# anssipv2.net
KiCad netlist of a schematic drawn in Altium Designer
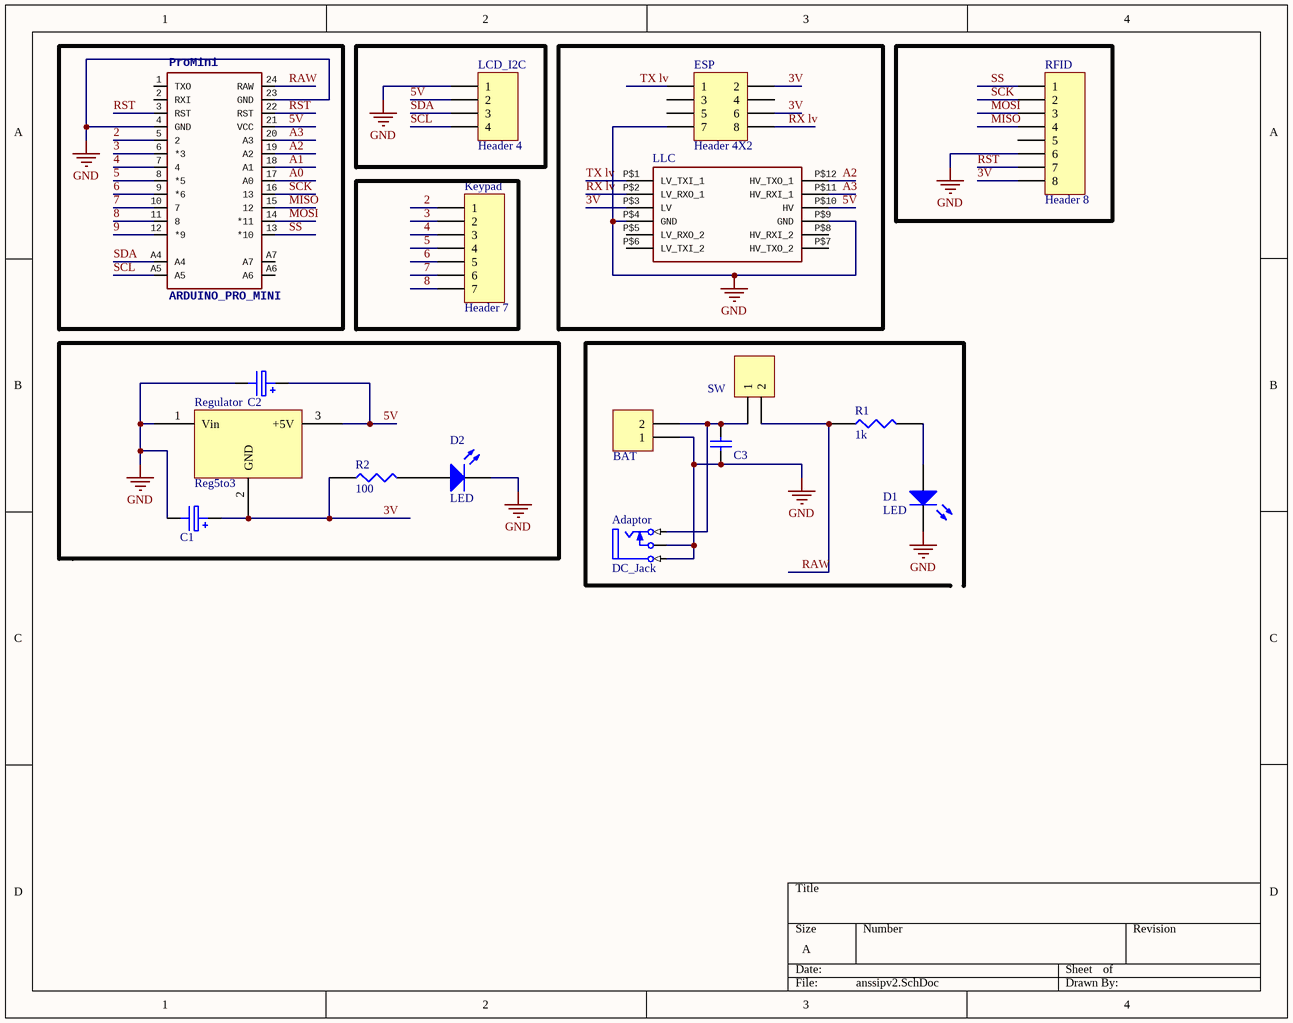
[diagram p0: anssipv2.SchDoc]

(export (version "E")
  (design (tool "Eeschema 10.0.6"))
  (components
    (comp (ref "Adaptor")
      (value "DC_Jack")
      (footprint "My_DC_Jack")
      (fields (field (name "PUBLISHER") "Altium Limited"))
      (libsource (lib "Mylib") (part "DC_Jack"))
    )
    (comp (ref "BAT")
      (value "Power Connector")
      (footprint "My_ Power_Connector")
      (description "white Power Connector")
      (libsource (lib "Mylib") (part "Power Connector"))
    )
    (comp (ref "C1")
      (value "10uF")
      (footprint "CAP 2.5/6.5")
      (description "Electrolytic Capacitor")
      (libsource (lib "Components") (part "CAP2"))
    )
    (comp (ref "C2")
      (value "10uF")
      (footprint "CAP 2.5/6.5")
      (description "Electrolytic Capacitor")
      (libsource (lib "Components") (part "CAP2"))
    )
    (comp (ref "C3")
      (value "Cap")
      (footprint "My_cap100n")
      (description "CAP-100Nf")
      (libsource (lib "Mylib") (part "Cap ceramic"))
    )
    (comp (ref "D1")
      (value "LED")
      (footprint "My_LED3MM")
      (description "Typical INFRARED GaAs LED")
      (fields (field (name "PUBLISHER") "Altium Limited"))
      (libsource (lib "Mylib") (part "LED"))
    )
    (comp (ref "D2")
      (value "LED")
      (footprint "My_LED3MM")
      (description "Typical INFRARED GaAs LED")
      (fields (field (name "PUBLISHER") "Altium Limited"))
      (libsource (lib "Mylib") (part "LED"))
    )
    (comp (ref "ESP")
      (value "Header 4X2")
      (footprint "HDR2X4")
      (description "Header, 4-Pin, Dual row")
      (fields (field (name "PUBLISHER") "Altium Limited"))
      (libsource (lib "Miscellaneous Connectors") (part "Header 4X2"))
    )
    (comp (ref "Keypad")
      (value "Header 7")
      (footprint "HDR1X7")
      (description "Header, 7-Pin")
      (fields (field (name "PUBLISHER") "Altium Limited"))
      (libsource (lib "Miscellaneous Connectors") (part "Header 7"))
    )
    (comp (ref "LCD_I2C")
      (value "Header 4")
      (footprint "HDR1X4")
      (description "Header, 4-Pin")
      (fields (field (name "PUBLISHER") "Altium Limited"))
      (libsource (lib "Miscellaneous Connectors") (part "Header 4"))
    )
    (comp (ref "LLC")
      (value "~")
      (footprint "LOGIC_LEVEL_CONVERTER")
      (libsource (lib "SparkFun-Boards") (part "LOGIC_LEVEL_CONVERTER"))
    )
    (comp (ref "ProMini")
      (value "ARDUINO_PRO_MINI")
      (footprint "ARDUINO_PRO_MINI")
      (libsource (lib "SparkFun-Boards") (part "ARDUINO_PRO_MINI"))
    )
    (comp (ref "R1")
      (value "1k")
      (footprint "My_axial-0.4")
      (description "resistor 1/4 wat")
      (libsource (lib "Mylib") (part "Res"))
    )
    (comp (ref "R2")
      (value "100")
      (footprint "My_axial-0.4")
      (description "resistor 1/4 wat")
      (fields (field (name "Comment") "1k"))
      (libsource (lib "Mylib") (part "Res"))
    )
    (comp (ref "Regulator")
      (value "Reg5to3")
      (footprint "My_TO-220")
      (description "Regulator")
      (libsource (lib "Mylib") (part "7805"))
    )
    (comp (ref "RFID")
      (value "Header 8")
      (footprint "HDR1X8")
      (description "Header, 8-Pin")
      (fields (field (name "PUBLISHER") "Altium Limited"))
      (libsource (lib "Miscellaneous Connectors") (part "Header 8"))
    )
    (comp (ref "SW")
      (value "Power Connector")
      (footprint "My_ Power_Connector")
      (description "white Power Connector")
      (libsource (lib "") (part "Power Connector_1"))
    )
  )
  (nets
    (net (code "1") (name "/2") (class "Default")
      (node (ref "Keypad") (pin "1") (pinfunction "1_1") (pintype "passive"))
      (node (ref "ProMini") (pin "5") (pinfunction "2_5") (pintype "passive"))
    )
    (net (code "2") (name "/3") (class "Default")
      (node (ref "Keypad") (pin "2") (pinfunction "2_2") (pintype "passive"))
      (node (ref "ProMini") (pin "6") (pinfunction "*3_6") (pintype "passive"))
    )
    (net (code "3") (name "/3V") (class "Default")
      (node (ref "C1") (pin "1") (pinfunction "1_1") (pintype "passive"))
      (node (ref "ESP") (pin "2") (pinfunction "2_2") (pintype "passive"))
      (node (ref "ESP") (pin "6") (pinfunction "6_6") (pintype "passive"))
      (node (ref "LLC") (pin "P$3") (pinfunction "LV_P$3") (pintype "passive"))
      (node (ref "R2") (pin "1") (pinfunction "1_1") (pintype "passive"))
      (node (ref "RFID") (pin "8") (pinfunction "8_8") (pintype "passive"))
      (node (ref "Regulator") (pin "2") (pinfunction "GND_2") (pintype "power_in"))
    )
    (net (code "4") (name "/4") (class "Default")
      (node (ref "Keypad") (pin "3") (pinfunction "3_3") (pintype "passive"))
      (node (ref "ProMini") (pin "7") (pinfunction "4_7") (pintype "passive"))
    )
    (net (code "5") (name "/5") (class "Default")
      (node (ref "Keypad") (pin "4") (pinfunction "4_4") (pintype "passive"))
      (node (ref "ProMini") (pin "8") (pinfunction "*5_8") (pintype "passive"))
    )
    (net (code "6") (name "/5V") (class "Default")
      (node (ref "C2") (pin "1") (pinfunction "1_1") (pintype "passive"))
      (node (ref "LCD_I2C") (pin "2") (pinfunction "2_2") (pintype "passive"))
      (node (ref "LLC") (pin "P$10") (pinfunction "HV_P$10") (pintype "passive"))
      (node (ref "ProMini") (pin "21") (pinfunction "VCC_21") (pintype "passive"))
      (node (ref "Regulator") (pin "3") (pinfunction "+5V_3") (pintype "power_in"))
    )
    (net (code "7") (name "/6") (class "Default")
      (node (ref "Keypad") (pin "5") (pinfunction "5_5") (pintype "passive"))
      (node (ref "ProMini") (pin "9") (pinfunction "*6_9") (pintype "passive"))
    )
    (net (code "8") (name "/7") (class "Default")
      (node (ref "Keypad") (pin "6") (pinfunction "6_6") (pintype "passive"))
      (node (ref "ProMini") (pin "10") (pinfunction "7_10") (pintype "passive"))
    )
    (net (code "9") (name "/8") (class "Default")
      (node (ref "Keypad") (pin "7") (pinfunction "7_7") (pintype "passive"))
      (node (ref "ProMini") (pin "11") (pinfunction "8_11") (pintype "passive"))
    )
    (net (code "10") (name "/9") (class "Default")
      (node (ref "ProMini") (pin "12") (pinfunction "*9_12") (pintype "passive"))
    )
    (net (code "11") (name "/A0") (class "Default")
      (node (ref "ProMini") (pin "17") (pinfunction "A0_17") (pintype "passive"))
    )
    (net (code "12") (name "/A1") (class "Default")
      (node (ref "ProMini") (pin "18") (pinfunction "A1_18") (pintype "passive"))
    )
    (net (code "13") (name "/A2") (class "Default")
      (node (ref "LLC") (pin "P$12") (pinfunction "HV_TXO_1_P$12") (pintype "passive"))
      (node (ref "ProMini") (pin "19") (pinfunction "A2_19") (pintype "passive"))
    )
    (net (code "14") (name "/A3") (class "Default")
      (node (ref "LLC") (pin "P$11") (pinfunction "HV_RXI_1_P$11") (pintype "passive"))
      (node (ref "ProMini") (pin "20") (pinfunction "A3_20") (pintype "passive"))
    )
    (net (code "15") (name "/MISO") (class "Default")
      (node (ref "ProMini") (pin "15") (pinfunction "12_15") (pintype "passive"))
      (node (ref "RFID") (pin "4") (pinfunction "4_4") (pintype "passive"))
    )
    (net (code "16") (name "/MOSI") (class "Default")
      (node (ref "ProMini") (pin "14") (pinfunction "*11_14") (pintype "passive"))
      (node (ref "RFID") (pin "3") (pinfunction "3_3") (pintype "passive"))
    )
    (net (code "17") (name "/RAW") (class "Default")
      (node (ref "ProMini") (pin "24") (pinfunction "RAW_24") (pintype "passive"))
      (node (ref "R1") (pin "1") (pinfunction "1_1") (pintype "passive"))
      (node (ref "SW") (pin "2") (pinfunction "2_2") (pintype "passive"))
    )
    (net (code "18") (name "/RST") (class "Default")
      (node (ref "ProMini") (pin "22") (pinfunction "RST_22") (pintype "passive"))
      (node (ref "ProMini") (pin "3") (pinfunction "RST_3") (pintype "passive"))
      (node (ref "RFID") (pin "7") (pinfunction "7_7") (pintype "passive"))
    )
    (net (code "19") (name "/RX lv") (class "Default")
      (node (ref "ESP") (pin "8") (pinfunction "8_8") (pintype "passive"))
      (node (ref "LLC") (pin "P$2") (pinfunction "LV_RXO_1_P$2") (pintype "passive"))
    )
    (net (code "20") (name "/SCK") (class "Default")
      (node (ref "ProMini") (pin "16") (pinfunction "13_16") (pintype "passive"))
      (node (ref "RFID") (pin "2") (pinfunction "2_2") (pintype "passive"))
    )
    (net (code "21") (name "/SCL") (class "Default")
      (node (ref "LCD_I2C") (pin "4") (pinfunction "4_4") (pintype "passive"))
      (node (ref "ProMini") (pin "A5") (pinfunction "A5_A5") (pintype "passive"))
    )
    (net (code "22") (name "/SDA") (class "Default")
      (node (ref "LCD_I2C") (pin "3") (pinfunction "3_3") (pintype "passive"))
      (node (ref "ProMini") (pin "A4") (pinfunction "A4_A4") (pintype "passive"))
    )
    (net (code "23") (name "/SS") (class "Default")
      (node (ref "ProMini") (pin "13") (pinfunction "*10_13") (pintype "passive"))
      (node (ref "RFID") (pin "1") (pinfunction "1_1") (pintype "passive"))
    )
    (net (code "24") (name "/TX lv") (class "Default")
      (node (ref "ESP") (pin "1") (pinfunction "1_1") (pintype "passive"))
      (node (ref "LLC") (pin "P$1") (pinfunction "LV_TXI_1_P$1") (pintype "passive"))
    )
    (net (code "25") (name "GND") (class "Default")
      (node (ref "Adaptor") (pin "2") (pinfunction "TN_2") (pintype "passive"))
      (node (ref "Adaptor") (pin "3") (pinfunction "S_3") (pintype "input"))
      (node (ref "BAT") (pin "1") (pinfunction "1_1") (pintype "passive"))
      (node (ref "C1") (pin "2") (pinfunction "2_2") (pintype "passive"))
      (node (ref "C2") (pin "2") (pinfunction "2_2") (pintype "passive"))
      (node (ref "C3") (pin "1") (pinfunction "1_1") (pintype "passive"))
      (node (ref "D1") (pin "K") (pinfunction "K_K") (pintype "passive"))
      (node (ref "D2") (pin "K") (pinfunction "K_K") (pintype "passive"))
      (node (ref "ESP") (pin "7") (pinfunction "7_7") (pintype "passive"))
      (node (ref "LCD_I2C") (pin "1") (pinfunction "1_1") (pintype "passive"))
      (node (ref "LLC") (pin "P$4") (pinfunction "GND_P$4") (pintype "passive"))
      (node (ref "LLC") (pin "P$9") (pinfunction "GND_P$9") (pintype "passive"))
      (node (ref "ProMini") (pin "23") (pinfunction "GND_23") (pintype "passive"))
      (node (ref "ProMini") (pin "4") (pinfunction "GND_4") (pintype "passive"))
      (node (ref "RFID") (pin "6") (pinfunction "6_6") (pintype "passive"))
      (node (ref "Regulator") (pin "1") (pinfunction "Vin_1") (pintype "power_in"))
    )
    (net (code "26") (name "Net-(Adaptor-T)") (class "Default")
      (node (ref "Adaptor") (pin "1") (pinfunction "T_1") (pintype "input"))
      (node (ref "BAT") (pin "2") (pinfunction "2_2") (pintype "passive"))
      (node (ref "C3") (pin "2") (pinfunction "2_2") (pintype "passive"))
      (node (ref "SW") (pin "1") (pinfunction "1_1") (pintype "passive"))
    )
    (net (code "27") (name "Net-(D1-PadA)") (class "Default")
      (node (ref "D1") (pin "A") (pinfunction "A_A") (pintype "passive"))
      (node (ref "R1") (pin "2") (pinfunction "2_2") (pintype "passive"))
    )
    (net (code "28") (name "Net-(D2-PadA)") (class "Default")
      (node (ref "D2") (pin "A") (pinfunction "A_A") (pintype "passive"))
      (node (ref "R2") (pin "2") (pinfunction "2_2") (pintype "passive"))
    )
    (net (code "29") (name "unconnected-(ESP-Pad3)") (class "Default")
      (node (ref "ESP") (pin "3") (pinfunction "3_3") (pintype "passive"))
    )
    (net (code "30") (name "unconnected-(ESP-Pad4)") (class "Default")
      (node (ref "ESP") (pin "4") (pinfunction "4_4") (pintype "passive"))
    )
    (net (code "31") (name "unconnected-(ESP-Pad5)") (class "Default")
      (node (ref "ESP") (pin "5") (pinfunction "5_5") (pintype "passive"))
    )
    (net (code "32") (name "unconnected-(LLC-HV_RXI_2-PadP$8)") (class "Default")
      (node (ref "LLC") (pin "P$8") (pinfunction "HV_RXI_2_P$8") (pintype "passive"))
    )
    (net (code "33") (name "unconnected-(LLC-HV_TXO_2-PadP$7)") (class "Default")
      (node (ref "LLC") (pin "P$7") (pinfunction "HV_TXO_2_P$7") (pintype "passive"))
    )
    (net (code "34") (name "unconnected-(LLC-LV_RXO_2-PadP$5)") (class "Default")
      (node (ref "LLC") (pin "P$5") (pinfunction "LV_RXO_2_P$5") (pintype "passive"))
    )
    (net (code "35") (name "unconnected-(LLC-LV_TXI_2-PadP$6)") (class "Default")
      (node (ref "LLC") (pin "P$6") (pinfunction "LV_TXI_2_P$6") (pintype "passive"))
    )
    (net (code "36") (name "unconnected-(ProMini-PadA6)") (class "Default")
      (node (ref "ProMini") (pin "A6") (pinfunction "A6_A6") (pintype "passive"))
    )
    (net (code "37") (name "unconnected-(ProMini-PadA7)") (class "Default")
      (node (ref "ProMini") (pin "A7") (pinfunction "A7_A7") (pintype "passive"))
    )
    (net (code "38") (name "unconnected-(ProMini-RXI-Pad2)") (class "Default")
      (node (ref "ProMini") (pin "2") (pinfunction "RXI_2") (pintype "passive"))
    )
    (net (code "39") (name "unconnected-(ProMini-TXO-Pad1)") (class "Default")
      (node (ref "ProMini") (pin "1") (pinfunction "TXO_1") (pintype "passive"))
    )
    (net (code "40") (name "unconnected-(RFID-Pad5)") (class "Default")
      (node (ref "RFID") (pin "5") (pinfunction "5_5") (pintype "passive"))
    )
  )
)
